# Codeshelf-0009_v01.net
KiCad netlist of a schematic drawn in EAGLE
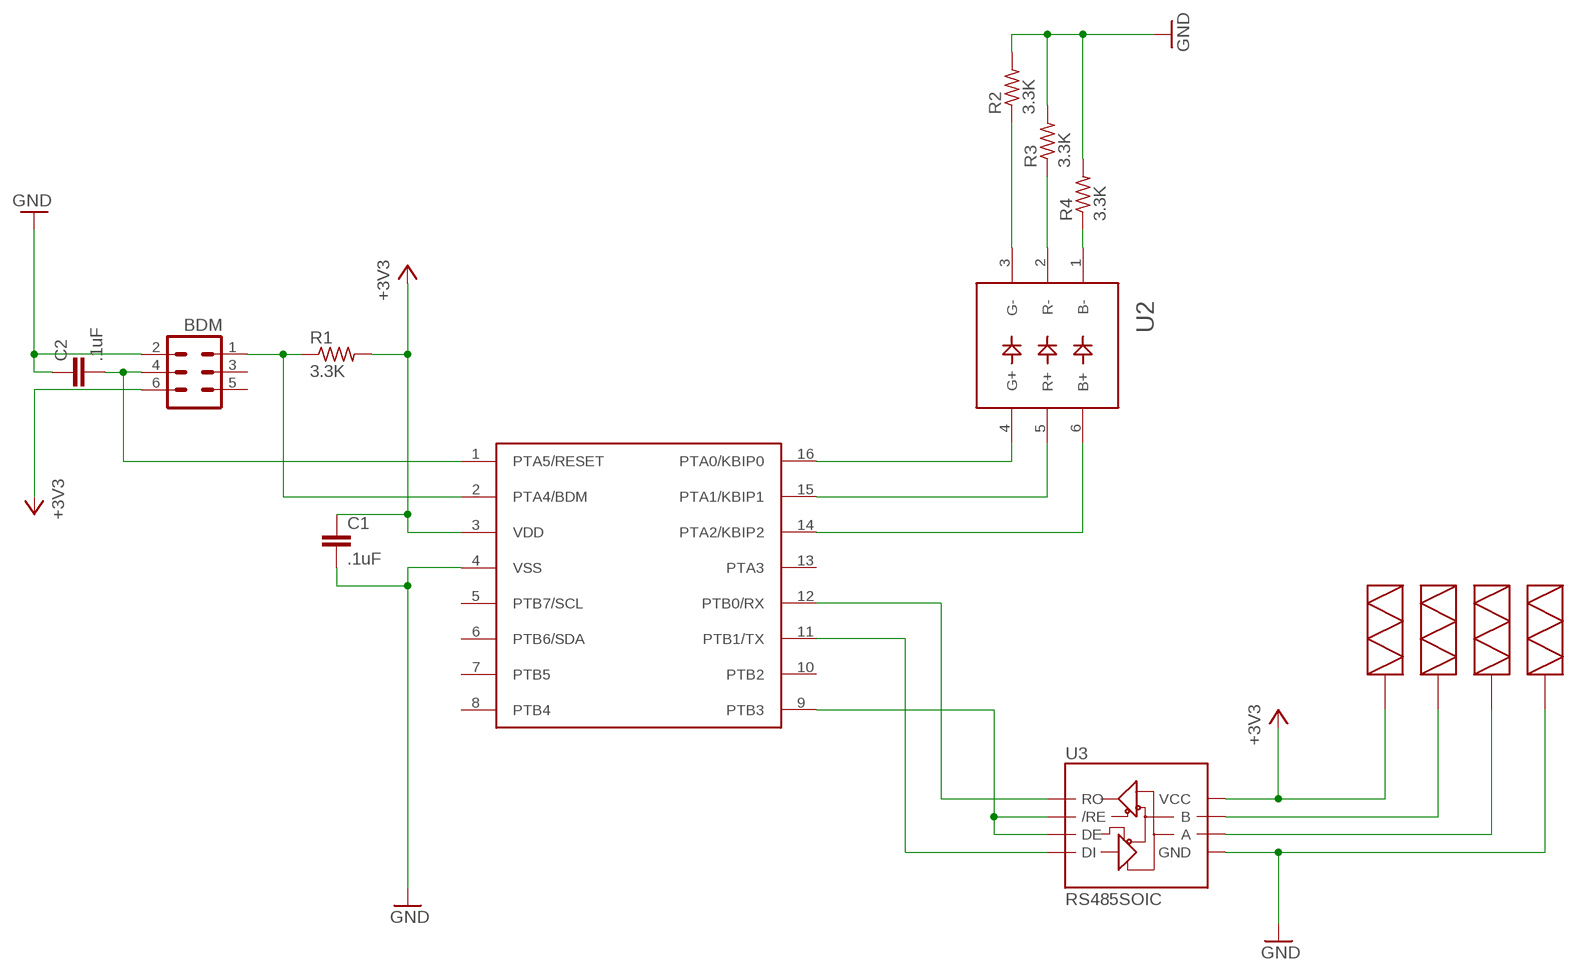
[diagram p0: schematic, sheet 1]

(export (version "E")
  (design (tool "Eeschema 10.0.6"))
  (components
    (comp (ref "BDM")
      (value "HEADER-3X2")
      (footprint "eagle-import:HEADER-3X2")
      (libsource (lib "eagle-import") (part "HEADER-3X2"))
    )
    (comp (ref "C1")
      (value ".1uF")
      (footprint "eagle-import:C0402")
      (libsource (lib "eagle-import") (part "RF-C0402"))
    )
    (comp (ref "C2")
      (value ".1uF")
      (footprint "eagle-import:C0402")
      (libsource (lib "eagle-import") (part "RF-C0402"))
    )
    (comp (ref "J1")
      (value "CONTACT-SPRING-S7071-42R")
      (footprint "eagle-import:CONTACT-SPRING-S1761")
      (libsource (lib "eagle-import") (part "CONTACT-SPRING-S1761"))
    )
    (comp (ref "J2")
      (value "CONTACT-SPRING-S7071-42R")
      (footprint "eagle-import:CONTACT-SPRING-S1761")
      (libsource (lib "eagle-import") (part "CONTACT-SPRING-S1761"))
    )
    (comp (ref "J3")
      (value "CONTACT-SPRING-S7071-42R")
      (footprint "eagle-import:CONTACT-SPRING-S1761")
      (libsource (lib "eagle-import") (part "CONTACT-SPRING-S1761"))
    )
    (comp (ref "J4")
      (value "CONTACT-SPRING-S7071-42R")
      (footprint "eagle-import:CONTACT-SPRING-S1761")
      (libsource (lib "eagle-import") (part "CONTACT-SPRING-S1761"))
    )
    (comp (ref "R1")
      (value "3.3K")
      (footprint "eagle-import:RF-R0402")
      (libsource (lib "eagle-import") (part "RF-R0402"))
    )
    (comp (ref "R2")
      (value "3.3K")
      (footprint "eagle-import:RF-R0402")
      (libsource (lib "eagle-import") (part "RF-R0402"))
    )
    (comp (ref "R3")
      (value "3.3K")
      (footprint "eagle-import:RF-R0402")
      (libsource (lib "eagle-import") (part "RF-R0402"))
    )
    (comp (ref "R4")
      (value "3.3K")
      (footprint "eagle-import:RF-R0402")
      (libsource (lib "eagle-import") (part "RF-R0402"))
    )
    (comp (ref "U1")
      (value "MC9S08QG-DT")
      (footprint "eagle-import:TSSOP16")
      (libsource (lib "eagle-import") (part "MC9S08QG-DT"))
    )
    (comp (ref "U2")
      (value "LED5060A")
      (footprint "eagle-import:PLCC-6")
      (libsource (lib "eagle-import") (part "LED5060A"))
    )
    (comp (ref "U3")
      (value "RS485SOIC")
      (footprint "eagle-import:SO08")
      (libsource (lib "eagle-import") (part "RS485SOIC"))
    )
  )
  (nets
    (net (code "1") (name "+3V3") (class "Default")
      (node (ref "BDM") (pin "6") (pinfunction "6_6") (pintype "passive"))
      (node (ref "C1") (pin "1") (pinfunction "1_1") (pintype "passive"))
      (node (ref "J1") (pin "P1") (pinfunction "P1_P1") (pintype "bidirectional"))
      (node (ref "R1") (pin "2") (pinfunction "2_2") (pintype "passive"))
      (node (ref "U1") (pin "3") (pinfunction "VDD_3") (pintype "bidirectional"))
      (node (ref "U3") (pin "8") (pinfunction "VCC_8") (pintype "bidirectional"))
    )
    (net (code "2") (name "GND") (class "Default")
      (node (ref "BDM") (pin "2") (pinfunction "2_2") (pintype "passive"))
      (node (ref "C1") (pin "2") (pinfunction "2_2") (pintype "passive"))
      (node (ref "C2") (pin "1") (pinfunction "1_1") (pintype "passive"))
      (node (ref "J4") (pin "P1") (pinfunction "P1_P1") (pintype "bidirectional"))
      (node (ref "R2") (pin "2") (pinfunction "2_2") (pintype "passive"))
      (node (ref "R3") (pin "2") (pinfunction "2_2") (pintype "passive"))
      (node (ref "R4") (pin "2") (pinfunction "2_2") (pintype "passive"))
      (node (ref "U1") (pin "4") (pinfunction "VSS_4") (pintype "bidirectional"))
      (node (ref "U3") (pin "5") (pinfunction "GND_5") (pintype "bidirectional"))
    )
    (net (code "3") (name "Net-(U1-PTA0{slash}KBIP0)") (class "Default")
      (node (ref "U1") (pin "16") (pinfunction "PTA0/KBIP0_16") (pintype "bidirectional"))
      (node (ref "U2") (pin "4") (pinfunction "G+_4") (pintype "bidirectional"))
    )
    (net (code "4") (name "Net-(U1-PTA1{slash}KBIP1)") (class "Default")
      (node (ref "U1") (pin "15") (pinfunction "PTA1/KBIP1_15") (pintype "bidirectional"))
      (node (ref "U2") (pin "5") (pinfunction "R+_5") (pintype "bidirectional"))
    )
    (net (code "5") (name "Net-(U1-PTA2{slash}KBIP2)") (class "Default")
      (node (ref "U1") (pin "14") (pinfunction "PTA2/KBIP2_14") (pintype "bidirectional"))
      (node (ref "U2") (pin "6") (pinfunction "B+_6") (pintype "bidirectional"))
    )
    (net (code "6") (name "Net-(U1-PTA4{slash}BDM)") (class "Default")
      (node (ref "BDM") (pin "1") (pinfunction "1_1") (pintype "passive"))
      (node (ref "R1") (pin "1") (pinfunction "1_1") (pintype "passive"))
      (node (ref "U1") (pin "2") (pinfunction "PTA4/BDM_2") (pintype "bidirectional"))
    )
    (net (code "7") (name "Net-(U1-PTA5{slash}RESET)") (class "Default")
      (node (ref "BDM") (pin "4") (pinfunction "4_4") (pintype "passive"))
      (node (ref "C2") (pin "2") (pinfunction "2_2") (pintype "passive"))
      (node (ref "U1") (pin "1") (pinfunction "PTA5/RESET_1") (pintype "bidirectional"))
    )
    (net (code "8") (name "Net-(U1-PTB0{slash}RX)") (class "Default")
      (node (ref "U1") (pin "12") (pinfunction "PTB0/RX_12") (pintype "bidirectional"))
      (node (ref "U3") (pin "1") (pinfunction "RO_1") (pintype "bidirectional"))
    )
    (net (code "9") (name "Net-(U1-PTB1{slash}TX)") (class "Default")
      (node (ref "U1") (pin "11") (pinfunction "PTB1/TX_11") (pintype "bidirectional"))
      (node (ref "U3") (pin "4") (pinfunction "DI_4") (pintype "bidirectional"))
    )
    (net (code "10") (name "Net-(U1-PTB3)") (class "Default")
      (node (ref "U1") (pin "9") (pinfunction "PTB3_9") (pintype "bidirectional"))
      (node (ref "U3") (pin "2") (pinfunction "/RE_2") (pintype "bidirectional"))
      (node (ref "U3") (pin "3") (pinfunction "DE_3") (pintype "bidirectional"))
    )
    (net (code "11") (name "Net-(U2-B-)") (class "Default")
      (node (ref "R4") (pin "1") (pinfunction "1_1") (pintype "passive"))
      (node (ref "U2") (pin "1") (pinfunction "B-_1") (pintype "bidirectional"))
    )
    (net (code "12") (name "Net-(U2-G-)") (class "Default")
      (node (ref "R2") (pin "1") (pinfunction "1_1") (pintype "passive"))
      (node (ref "U2") (pin "3") (pinfunction "G-_3") (pintype "bidirectional"))
    )
    (net (code "13") (name "Net-(U2-R-)") (class "Default")
      (node (ref "R3") (pin "1") (pinfunction "1_1") (pintype "passive"))
      (node (ref "U2") (pin "2") (pinfunction "R-_2") (pintype "bidirectional"))
    )
    (net (code "14") (name "Net-(U3-A)") (class "Default")
      (node (ref "J3") (pin "P1") (pinfunction "P1_P1") (pintype "bidirectional"))
      (node (ref "U3") (pin "6") (pinfunction "A_6") (pintype "bidirectional"))
    )
    (net (code "15") (name "Net-(U3-B)") (class "Default")
      (node (ref "J2") (pin "P1") (pinfunction "P1_P1") (pintype "bidirectional"))
      (node (ref "U3") (pin "7") (pinfunction "B_7") (pintype "bidirectional"))
    )
    (net (code "16") (name "unconnected-(BDM-Pad3)") (class "Default")
      (node (ref "BDM") (pin "3") (pinfunction "3_3") (pintype "passive"))
    )
    (net (code "17") (name "unconnected-(BDM-Pad5)") (class "Default")
      (node (ref "BDM") (pin "5") (pinfunction "5_5") (pintype "passive"))
    )
    (net (code "18") (name "unconnected-(U1-PTA3-Pad13)") (class "Default")
      (node (ref "U1") (pin "13") (pinfunction "PTA3_13") (pintype "bidirectional"))
    )
    (net (code "19") (name "unconnected-(U1-PTB2-Pad10)") (class "Default")
      (node (ref "U1") (pin "10") (pinfunction "PTB2_10") (pintype "bidirectional"))
    )
    (net (code "20") (name "unconnected-(U1-PTB4-Pad8)") (class "Default")
      (node (ref "U1") (pin "8") (pinfunction "PTB4_8") (pintype "bidirectional"))
    )
    (net (code "21") (name "unconnected-(U1-PTB5-Pad7)") (class "Default")
      (node (ref "U1") (pin "7") (pinfunction "PTB5_7") (pintype "bidirectional"))
    )
    (net (code "22") (name "unconnected-(U1-PTB6{slash}SDA-Pad6)") (class "Default")
      (node (ref "U1") (pin "6") (pinfunction "PTB6/SDA_6") (pintype "bidirectional"))
    )
    (net (code "23") (name "unconnected-(U1-PTB7{slash}SCL-Pad5)") (class "Default")
      (node (ref "U1") (pin "5") (pinfunction "PTB7/SCL_5") (pintype "bidirectional"))
    )
  )
)
